# RJ45_Sheet.net
KiCad netlist of a schematic drawn in Altium Designer
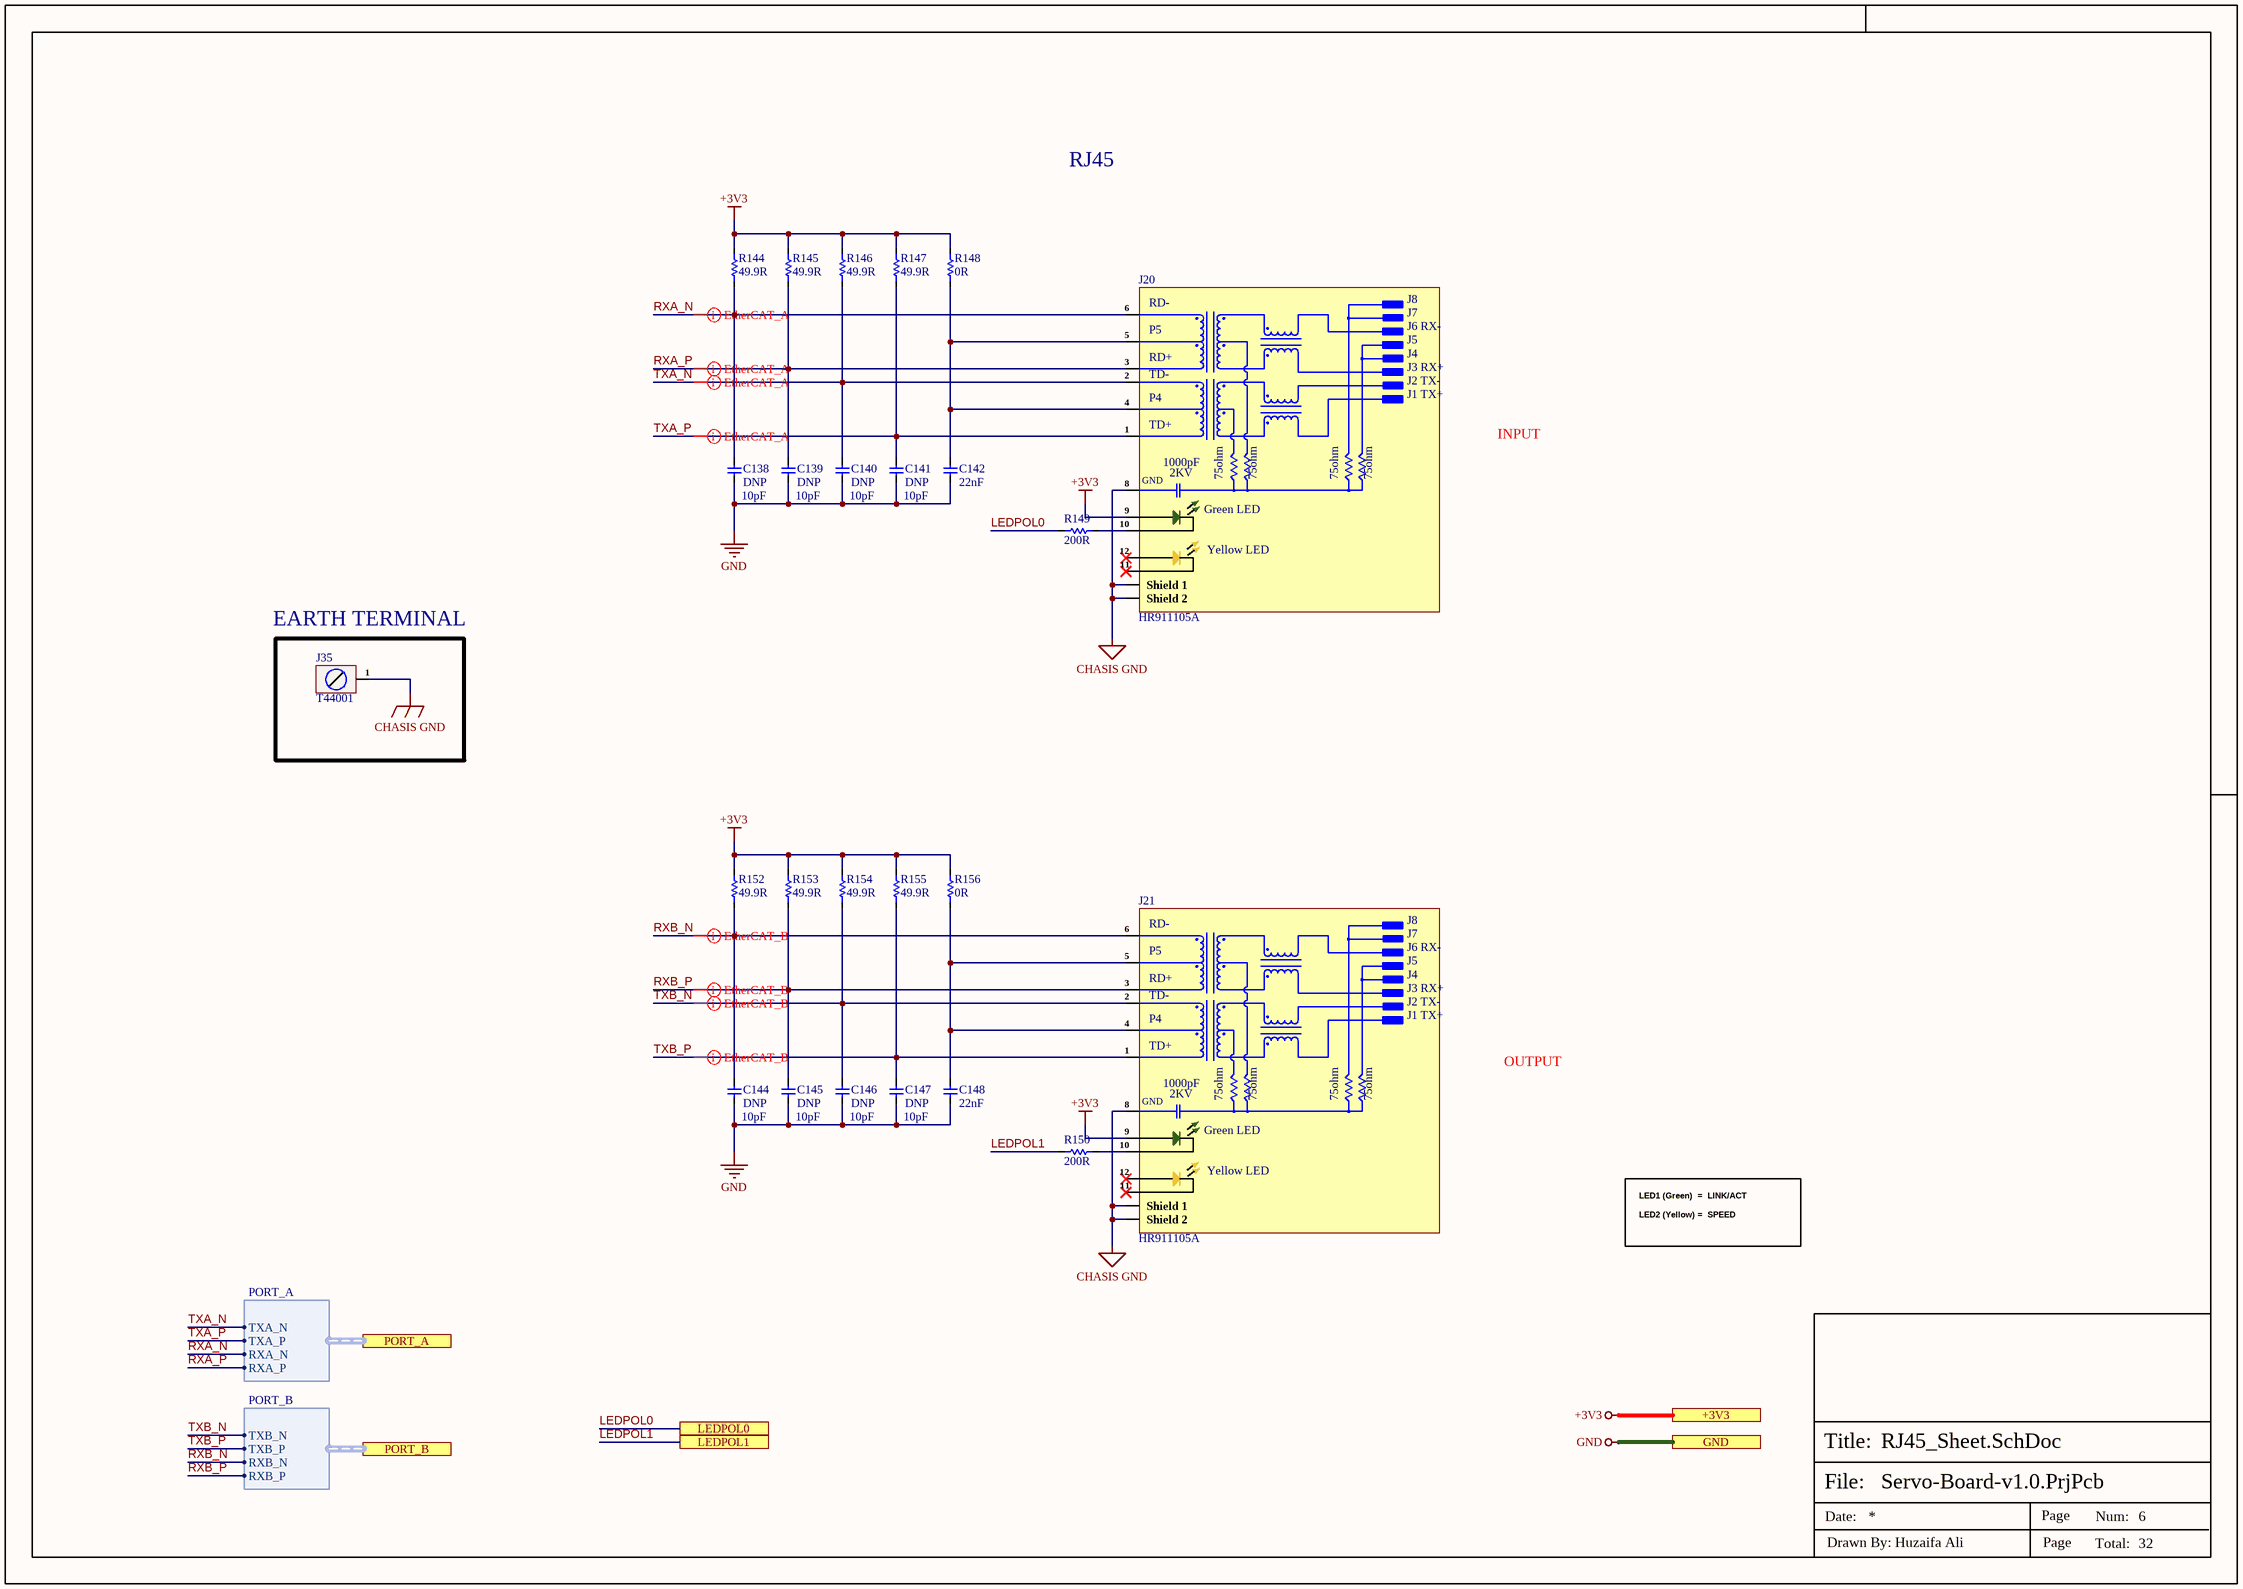
[diagram p0: RJ45_Sheet.SchDoc]

(export (version "E")
  (design (tool "Eeschema 10.0.6"))
  (components
    (comp (ref "C138")
      (value "DNP")
      (footprint "Cap-0402")
      (description "CAP CER 10PF 50V C0G/NP0 0402")
      (fields
        (field (name "MANUFACTURER") "Murata")
        (field (name "MANUFACTURER PART NUMBER") "GRM1555C1H100JA01D")
      )
      (libsource (lib "eSpark Libraries") (part "GRM1555C1H100JA01D"))
    )
    (comp (ref "C139")
      (value "DNP")
      (footprint "Cap-0402")
      (description "CAP CER 10PF 50V C0G/NP0 0402")
      (fields
        (field (name "MANUFACTURER") "Murata")
        (field (name "MANUFACTURER PART NUMBER") "GRM1555C1H100JA01D")
      )
      (libsource (lib "eSpark Libraries") (part "GRM1555C1H100JA01D"))
    )
    (comp (ref "C140")
      (value "DNP")
      (footprint "Cap-0402")
      (description "CAP CER 10PF 50V C0G/NP0 0402")
      (fields
        (field (name "MANUFACTURER") "Murata")
        (field (name "MANUFACTURER PART NUMBER") "GRM1555C1H100JA01D")
      )
      (libsource (lib "eSpark Libraries") (part "GRM1555C1H100JA01D"))
    )
    (comp (ref "C141")
      (value "DNP")
      (footprint "Cap-0402")
      (description "CAP CER 10PF 50V C0G/NP0 0402")
      (fields
        (field (name "MANUFACTURER") "Murata")
        (field (name "MANUFACTURER PART NUMBER") "GRM1555C1H100JA01D")
      )
      (libsource (lib "eSpark Libraries") (part "GRM1555C1H100JA01D"))
    )
    (comp (ref "C142")
      (value "22nF")
      (footprint "Cap-0402")
      (description "CAP CER 0.022UF 16V X7R 0402")
      (fields
        (field (name "MANUFACTURER") "Yageo")
        (field (name "MANUFACTURER PART NUMBER") "CC0402JRX7R7BB223")
      )
      (libsource (lib "eSpark Libraries") (part "CC0402JRX7R7BB223"))
    )
    (comp (ref "C144")
      (value "DNP")
      (footprint "Cap-0402")
      (description "CAP CER 10PF 50V C0G/NP0 0402")
      (fields
        (field (name "MANUFACTURER") "Murata")
        (field (name "MANUFACTURER PART NUMBER") "GRM1555C1H100JA01D")
      )
      (libsource (lib "eSpark Libraries") (part "GRM1555C1H100JA01D"))
    )
    (comp (ref "C145")
      (value "DNP")
      (footprint "Cap-0402")
      (description "CAP CER 10PF 50V C0G/NP0 0402")
      (fields
        (field (name "MANUFACTURER") "Murata")
        (field (name "MANUFACTURER PART NUMBER") "GRM1555C1H100JA01D")
      )
      (libsource (lib "eSpark Libraries") (part "GRM1555C1H100JA01D"))
    )
    (comp (ref "C146")
      (value "DNP")
      (footprint "Cap-0402")
      (description "CAP CER 10PF 50V C0G/NP0 0402")
      (fields
        (field (name "MANUFACTURER") "Murata")
        (field (name "MANUFACTURER PART NUMBER") "GRM1555C1H100JA01D")
      )
      (libsource (lib "eSpark Libraries") (part "GRM1555C1H100JA01D"))
    )
    (comp (ref "C147")
      (value "DNP")
      (footprint "Cap-0402")
      (description "CAP CER 10PF 50V C0G/NP0 0402")
      (fields
        (field (name "MANUFACTURER") "Murata")
        (field (name "MANUFACTURER PART NUMBER") "GRM1555C1H100JA01D")
      )
      (libsource (lib "eSpark Libraries") (part "GRM1555C1H100JA01D"))
    )
    (comp (ref "C148")
      (value "22nF")
      (footprint "Cap-0402")
      (description "CAP CER 0.022UF 16V X7R 0402")
      (fields
        (field (name "MANUFACTURER") "Yageo")
        (field (name "MANUFACTURER PART NUMBER") "CC0402JRX7R7BB223")
      )
      (libsource (lib "eSpark Libraries") (part "CC0402JRX7R7BB223"))
    )
    (comp (ref "J20")
      (value "HR911105A")
      (footprint "HR911105A")
      (description "RJ45 RJReceptacle 1 WithLED Plugin Ethernet Connectors/Modular Connectors (RJ45 RJ11) ROHS")
      (fields (field (name "MANUFACTURER") "HANRUN") (field (name "LCSC PART NUMBER") "C12074"))
      (libsource (lib "eSpark Libraries") (part "HR911105A"))
    )
    (comp (ref "J21")
      (value "HR911105A")
      (footprint "HR911105A")
      (description "RJ45 RJReceptacle 1 WithLED Plugin Ethernet Connectors/Modular Connectors (RJ45 RJ11) ROHS")
      (fields (field (name "MANUFACTURER") "HANRUN") (field (name "LCSC PART NUMBER") "C12074"))
      (libsource (lib "eSpark Libraries") (part "HR911105A"))
    )
    (comp (ref "J35")
      (value "T44001")
      (footprint "T44001")
      (description "M4 Plugin PCB Welding Terminal ROHS")
      (fields (field (name "MANUFACTURER") "XFCN"))
      (libsource (lib "eSpark Libraries") (part "T44001"))
    )
    (comp (ref "R144")
      (value "49.9R")
      (footprint "Res-0603")
      (description "RES 49.9 OHM 1% 1/10W 0603")
      (fields
        (field (name "MANUFACTURER") "Yageo")
        (field (name "MANUFACTURER PART NUMBER") "RC0603FR-0749R9L")
      )
      (libsource (lib "eSpark Libraries") (part "RC0603FR-0749R9L"))
    )
    (comp (ref "R145")
      (value "49.9R")
      (footprint "Res-0603")
      (description "RES 49.9 OHM 1% 1/10W 0603")
      (fields
        (field (name "MANUFACTURER") "Yageo")
        (field (name "MANUFACTURER PART NUMBER") "RC0603FR-0749R9L")
      )
      (libsource (lib "eSpark Libraries") (part "RC0603FR-0749R9L"))
    )
    (comp (ref "R146")
      (value "49.9R")
      (footprint "Res-0603")
      (description "RES 49.9 OHM 1% 1/10W 0603")
      (fields
        (field (name "MANUFACTURER") "Yageo")
        (field (name "MANUFACTURER PART NUMBER") "RC0603FR-0749R9L")
      )
      (libsource (lib "eSpark Libraries") (part "RC0603FR-0749R9L"))
    )
    (comp (ref "R147")
      (value "49.9R")
      (footprint "Res-0603")
      (description "RES 49.9 OHM 1% 1/10W 0603")
      (fields
        (field (name "MANUFACTURER") "Yageo")
        (field (name "MANUFACTURER PART NUMBER") "RC0603FR-0749R9L")
      )
      (libsource (lib "eSpark Libraries") (part "RC0603FR-0749R9L"))
    )
    (comp (ref "R148")
      (value "0R")
      (footprint "Res-0402")
      (description "RESISTOR 0402 JUMPER ZERO OHM")
      (fields
        (field (name "MANUFACTURER") "Yageo")
        (field (name "MANUFACTURER PART NUMBER") "AC0402FR-070RL")
      )
      (libsource (lib "eSpark Libraries") (part "AC0402FR-070RL"))
    )
    (comp (ref "R149")
      (value "200R")
      (footprint "Res-0402")
      (description "RES 200 OHM 1% 1/16W 0402")
      (fields
        (field (name "MANUFACTURER") "Yageo")
        (field (name "MANUFACTURER PART NUMBER") "RC0402FR-07200RL")
      )
      (libsource (lib "eSpark Libraries") (part "RC0402FR-07200RL"))
    )
    (comp (ref "R150")
      (value "200R")
      (footprint "Res-0402")
      (description "RES 200 OHM 1% 1/16W 0402")
      (fields
        (field (name "MANUFACTURER") "Yageo")
        (field (name "MANUFACTURER PART NUMBER") "RC0402FR-07200RL")
      )
      (libsource (lib "eSpark Libraries") (part "RC0402FR-07200RL"))
    )
    (comp (ref "R152")
      (value "49.9R")
      (footprint "Res-0603")
      (description "RES 49.9 OHM 1% 1/10W 0603")
      (fields
        (field (name "MANUFACTURER") "Yageo")
        (field (name "MANUFACTURER PART NUMBER") "RC0603FR-0749R9L")
      )
      (libsource (lib "eSpark Libraries") (part "RC0603FR-0749R9L"))
    )
    (comp (ref "R153")
      (value "49.9R")
      (footprint "Res-0603")
      (description "RES 49.9 OHM 1% 1/10W 0603")
      (fields
        (field (name "MANUFACTURER") "Yageo")
        (field (name "MANUFACTURER PART NUMBER") "RC0603FR-0749R9L")
      )
      (libsource (lib "eSpark Libraries") (part "RC0603FR-0749R9L"))
    )
    (comp (ref "R154")
      (value "49.9R")
      (footprint "Res-0603")
      (description "RES 49.9 OHM 1% 1/10W 0603")
      (fields
        (field (name "MANUFACTURER") "Yageo")
        (field (name "MANUFACTURER PART NUMBER") "RC0603FR-0749R9L")
      )
      (libsource (lib "eSpark Libraries") (part "RC0603FR-0749R9L"))
    )
    (comp (ref "R155")
      (value "49.9R")
      (footprint "Res-0603")
      (description "RES 49.9 OHM 1% 1/10W 0603")
      (fields
        (field (name "MANUFACTURER") "Yageo")
        (field (name "MANUFACTURER PART NUMBER") "RC0603FR-0749R9L")
      )
      (libsource (lib "eSpark Libraries") (part "RC0603FR-0749R9L"))
    )
    (comp (ref "R156")
      (value "0R")
      (footprint "Res-0402")
      (description "RESISTOR 0402 JUMPER ZERO OHM")
      (fields
        (field (name "MANUFACTURER") "Yageo")
        (field (name "MANUFACTURER PART NUMBER") "AC0402FR-070RL")
      )
      (libsource (lib "eSpark Libraries") (part "AC0402FR-070RL"))
    )
  )
  (nets
    (net (code "3") (name "+3V3") (class "Default")
      (node (ref "J20") (pin "9") (pinfunction "ANODE_9") (pintype "passive"))
      (node (ref "J21") (pin "9") (pinfunction "ANODE_9") (pintype "passive"))
      (node (ref "R144") (pin "2") (pinfunction "2_2") (pintype "passive"))
      (node (ref "R145") (pin "2") (pinfunction "2_2") (pintype "passive"))
      (node (ref "R146") (pin "2") (pinfunction "2_2") (pintype "passive"))
      (node (ref "R147") (pin "2") (pinfunction "2_2") (pintype "passive"))
      (node (ref "R148") (pin "2") (pinfunction "2_2") (pintype "passive"))
      (node (ref "R152") (pin "2") (pinfunction "2_2") (pintype "passive"))
      (node (ref "R153") (pin "2") (pinfunction "2_2") (pintype "passive"))
      (node (ref "R154") (pin "2") (pinfunction "2_2") (pintype "passive"))
      (node (ref "R155") (pin "2") (pinfunction "2_2") (pintype "passive"))
      (node (ref "R156") (pin "2") (pinfunction "2_2") (pintype "passive"))
    )
    (net (code "4") (name "/LEDPOL0") (class "Default")
      (node (ref "R149") (pin "1") (pinfunction "1_1") (pintype "passive"))
    )
    (net (code "5") (name "/LEDPOL1") (class "Default")
      (node (ref "R150") (pin "1") (pinfunction "1_1") (pintype "passive"))
    )
    (net (code "6") (name "/RXA_N") (class "Default")
      (node (ref "C138") (pin "2") (pinfunction "2_2") (pintype "passive"))
      (node (ref "J20") (pin "6") (pinfunction "RD-_6") (pintype "passive"))
      (node (ref "R144") (pin "1") (pinfunction "1_1") (pintype "passive"))
    )
    (net (code "7") (name "/RXA_P") (class "Default")
      (node (ref "C139") (pin "2") (pinfunction "2_2") (pintype "passive"))
      (node (ref "J20") (pin "3") (pinfunction "RD+_3") (pintype "passive"))
      (node (ref "R145") (pin "1") (pinfunction "1_1") (pintype "passive"))
    )
    (net (code "8") (name "/RXB_N") (class "Default")
      (node (ref "C144") (pin "2") (pinfunction "2_2") (pintype "passive"))
      (node (ref "J21") (pin "6") (pinfunction "RD-_6") (pintype "passive"))
      (node (ref "R152") (pin "1") (pinfunction "1_1") (pintype "passive"))
    )
    (net (code "9") (name "/RXB_P") (class "Default")
      (node (ref "C145") (pin "2") (pinfunction "2_2") (pintype "passive"))
      (node (ref "J21") (pin "3") (pinfunction "RD+_3") (pintype "passive"))
      (node (ref "R153") (pin "1") (pinfunction "1_1") (pintype "passive"))
    )
    (net (code "10") (name "/TXA_N") (class "Default")
      (node (ref "C140") (pin "2") (pinfunction "2_2") (pintype "passive"))
      (node (ref "J20") (pin "2") (pinfunction "TD-_2") (pintype "passive"))
      (node (ref "R146") (pin "1") (pinfunction "1_1") (pintype "passive"))
    )
    (net (code "11") (name "/TXA_P") (class "Default")
      (node (ref "C141") (pin "2") (pinfunction "2_2") (pintype "passive"))
      (node (ref "J20") (pin "1") (pinfunction "TD+_1") (pintype "passive"))
      (node (ref "R147") (pin "1") (pinfunction "1_1") (pintype "passive"))
    )
    (net (code "12") (name "/TXB_N") (class "Default")
      (node (ref "C146") (pin "2") (pinfunction "2_2") (pintype "passive"))
      (node (ref "J21") (pin "2") (pinfunction "TD-_2") (pintype "passive"))
      (node (ref "R154") (pin "1") (pinfunction "1_1") (pintype "passive"))
    )
    (net (code "13") (name "/TXB_P") (class "Default")
      (node (ref "C147") (pin "2") (pinfunction "2_2") (pintype "passive"))
      (node (ref "J21") (pin "1") (pinfunction "TD+_1") (pintype "passive"))
      (node (ref "R155") (pin "1") (pinfunction "1_1") (pintype "passive"))
    )
    (net (code "16") (name "CHASIS GND") (class "Default")
      (node (ref "J20") (pin "8") (pinfunction "GND_8") (pintype "power_in"))
      (node (ref "J20") (pin "Shield_1") (pinfunction "Shield_1_Shield_1") (pintype "passive"))
      (node (ref "J20") (pin "Shield_2") (pinfunction "Shield_2_Shield_2") (pintype "passive"))
      (node (ref "J21") (pin "8") (pinfunction "GND_8") (pintype "power_in"))
      (node (ref "J21") (pin "Shield_1") (pinfunction "Shield_1_Shield_1") (pintype "passive"))
      (node (ref "J21") (pin "Shield_2") (pinfunction "Shield_2_Shield_2") (pintype "passive"))
      (node (ref "J35") (pin "1") (pinfunction "1_1") (pintype "passive"))
    )
    (net (code "17") (name "GND") (class "Default")
      (node (ref "C138") (pin "1") (pinfunction "1_1") (pintype "passive"))
      (node (ref "C139") (pin "1") (pinfunction "1_1") (pintype "passive"))
      (node (ref "C140") (pin "1") (pinfunction "1_1") (pintype "passive"))
      (node (ref "C141") (pin "1") (pinfunction "1_1") (pintype "passive"))
      (node (ref "C142") (pin "1") (pinfunction "1_1") (pintype "passive"))
      (node (ref "C144") (pin "1") (pinfunction "1_1") (pintype "passive"))
      (node (ref "C145") (pin "1") (pinfunction "1_1") (pintype "passive"))
      (node (ref "C146") (pin "1") (pinfunction "1_1") (pintype "passive"))
      (node (ref "C147") (pin "1") (pinfunction "1_1") (pintype "passive"))
      (node (ref "C148") (pin "1") (pinfunction "1_1") (pintype "passive"))
    )
    (net (code "18") (name "Net-(J20-CATHODE-Pad10)") (class "Default")
      (node (ref "J20") (pin "10") (pinfunction "CATHODE_10") (pintype "passive"))
      (node (ref "R149") (pin "2") (pinfunction "2_2") (pintype "passive"))
    )
    (net (code "19") (name "Net-(J20-P4)") (class "Default")
      (node (ref "C142") (pin "2") (pinfunction "2_2") (pintype "passive"))
      (node (ref "J20") (pin "4") (pinfunction "P4_4") (pintype "passive"))
      (node (ref "J20") (pin "5") (pinfunction "P5_5") (pintype "passive"))
      (node (ref "R148") (pin "1") (pinfunction "1_1") (pintype "passive"))
    )
    (net (code "20") (name "Net-(J21-CATHODE-Pad10)") (class "Default")
      (node (ref "J21") (pin "10") (pinfunction "CATHODE_10") (pintype "passive"))
      (node (ref "R150") (pin "2") (pinfunction "2_2") (pintype "passive"))
    )
    (net (code "21") (name "Net-(J21-P4)") (class "Default")
      (node (ref "C148") (pin "2") (pinfunction "2_2") (pintype "passive"))
      (node (ref "J21") (pin "4") (pinfunction "P4_4") (pintype "passive"))
      (node (ref "J21") (pin "5") (pinfunction "P5_5") (pintype "passive"))
      (node (ref "R156") (pin "1") (pinfunction "1_1") (pintype "passive"))
    )
    (net (code "22") (name "unconnected-(J20-ANODE-Pad12)") (class "Default")
      (node (ref "J20") (pin "12") (pinfunction "ANODE_12") (pintype "passive+no_connect"))
    )
    (net (code "23") (name "unconnected-(J20-CATHODE-Pad11)") (class "Default")
      (node (ref "J20") (pin "11") (pinfunction "CATHODE_11") (pintype "passive+no_connect"))
    )
    (net (code "24") (name "unconnected-(J21-ANODE-Pad12)") (class "Default")
      (node (ref "J21") (pin "12") (pinfunction "ANODE_12") (pintype "passive+no_connect"))
    )
    (net (code "25") (name "unconnected-(J21-CATHODE-Pad11)") (class "Default")
      (node (ref "J21") (pin "11") (pinfunction "CATHODE_11") (pintype "passive+no_connect"))
    )
  )
)
